# RPI_PICO_WH_PCB.net
KiCad netlist of a schematic drawn in EAGLE
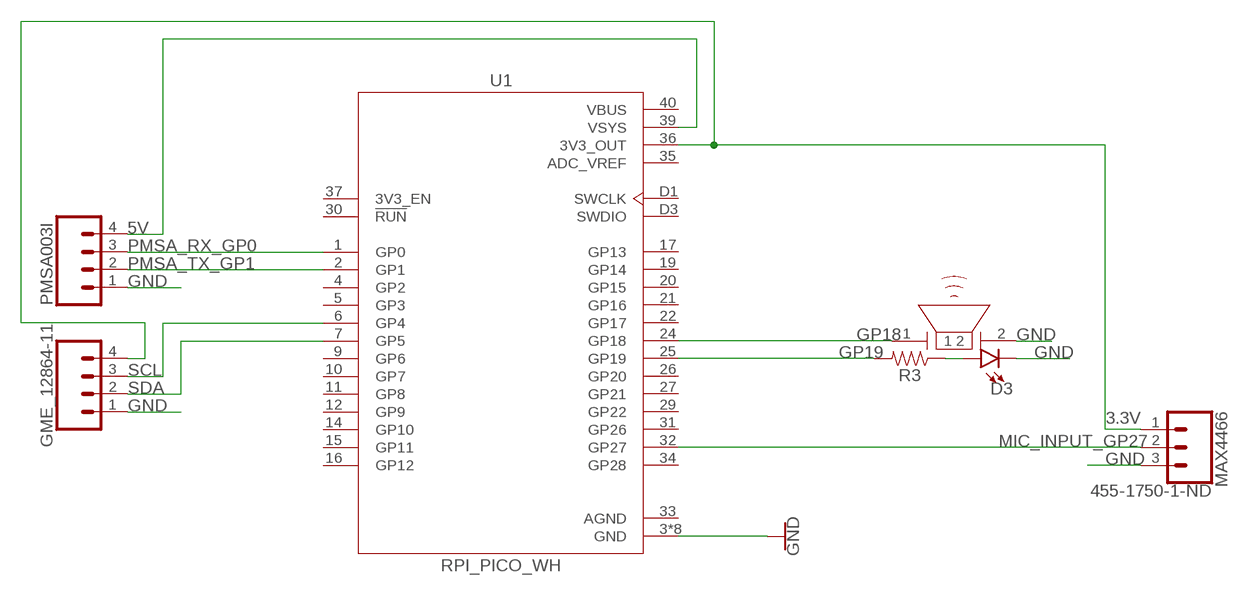
[diagram p0: schematic, sheet 1]

(export (version "E")
  (design (tool "Eeschema 10.0.6"))
  (components
    (comp (ref "D3")
      (value "LED5MM")
      (footprint "eagle-import:LED_5MM")
      (libsource (lib "eagle-import") (part "LED5MM"))
    )
    (comp (ref "GME_12864-11")
      (value "CONN_04PTH")
      (footprint "eagle-import:1X04")
      (libsource (lib "eagle-import") (part "CONN_04PTH"))
    )
    (comp (ref "LS1")
      (value "PIEZO")
      (footprint "eagle-import:PIEZO")
      (libsource (lib "eagle-import") (part "PIEZO"))
    )
    (comp (ref "MAX4466")
      (value "455-1750-1-ND")
      (footprint "eagle-import:1X03")
      (libsource (lib "eagle-import") (part "CONN_03"))
    )
    (comp (ref "PMSA003I")
      (value "CONN_04PTH")
      (footprint "eagle-import:1X04")
      (libsource (lib "eagle-import") (part "CONN_04PTH"))
    )
    (comp (ref "R3")
      (value "RESISTORAXIAL-0.3")
      (footprint "eagle-import:AXIAL-0.3")
      (libsource (lib "eagle-import") (part "RESISTORAXIAL-0.3"))
    )
    (comp (ref "U1")
      (value "RPI_PICO_WH")
      (footprint "eagle-import:PI_PICO_WH")
      (fields (field (name "MANUFACTURER") "Raspberry Pi") (field (name "MPN") "SC0919"))
      (libsource (lib "eagle-import") (part "RPI_PICO_WH"))
    )
  )
  (nets
    (net (code "1") (name "/3.3V") (class "Default")
      (node (ref "GME_12864-11") (pin "4") (pinfunction "4_4") (pintype "passive"))
      (node (ref "MAX4466") (pin "1") (pinfunction "1_1") (pintype "passive"))
      (node (ref "U1") (pin "36") (pinfunction "3V3_OUT_36") (pintype "power_in"))
    )
    (net (code "2") (name "/5V") (class "Default")
      (node (ref "PMSA003I") (pin "4") (pinfunction "4_4") (pintype "passive"))
      (node (ref "U1") (pin "39") (pinfunction "VSYS_39") (pintype "power_in"))
    )
    (net (code "3") (name "/ADC_VREF") (class "Default")
      (node (ref "U1") (pin "35") (pinfunction "ADC_VREF_35") (pintype "power_in"))
    )
    (net (code "4") (name "/AGND") (class "Default")
      (node (ref "U1") (pin "33") (pinfunction "AGND_33") (pintype "power_in"))
    )
    (net (code "5") (name "/GP18") (class "Default")
      (node (ref "LS1") (pin "1") (pinfunction "1_1") (pintype "passive"))
      (node (ref "U1") (pin "24") (pinfunction "GP18_24") (pintype "bidirectional"))
    )
    (net (code "6") (name "/GP19") (class "Default")
      (node (ref "R3") (pin "P$2") (pinfunction "2_P$2") (pintype "passive"))
      (node (ref "U1") (pin "25") (pinfunction "GP19_25") (pintype "bidirectional"))
    )
    (net (code "7") (name "/MIC_INPUT_GP27") (class "Default")
      (node (ref "MAX4466") (pin "2") (pinfunction "2_2") (pintype "passive"))
      (node (ref "U1") (pin "32") (pinfunction "GP27_32") (pintype "bidirectional"))
    )
    (net (code "8") (name "/PMSA_RX_GP0") (class "Default")
      (node (ref "PMSA003I") (pin "3") (pinfunction "3_3") (pintype "passive"))
      (node (ref "U1") (pin "1") (pinfunction "GP0_1") (pintype "bidirectional"))
    )
    (net (code "9") (name "/PMSA_TX_GP1") (class "Default")
      (node (ref "PMSA003I") (pin "2") (pinfunction "2_2") (pintype "passive"))
      (node (ref "U1") (pin "2") (pinfunction "GP1_2") (pintype "bidirectional"))
    )
    (net (code "10") (name "/SCL") (class "Default")
      (node (ref "GME_12864-11") (pin "3") (pinfunction "3_3") (pintype "passive"))
      (node (ref "U1") (pin "6") (pinfunction "GP4_6") (pintype "bidirectional"))
    )
    (net (code "11") (name "/SDA") (class "Default")
      (node (ref "GME_12864-11") (pin "2") (pinfunction "2_2") (pintype "passive"))
      (node (ref "U1") (pin "7") (pinfunction "GP5_7") (pintype "bidirectional"))
    )
    (net (code "12") (name "/VBUS") (class "Default")
      (node (ref "U1") (pin "40") (pinfunction "VBUS_40") (pintype "power_in"))
    )
    (net (code "13") (name "GND") (class "Default")
      (node (ref "D3") (pin "K") (pinfunction "C_K") (pintype "passive"))
      (node (ref "GME_12864-11") (pin "1") (pinfunction "1_1") (pintype "passive"))
      (node (ref "LS1") (pin "2") (pinfunction "2_2") (pintype "passive"))
      (node (ref "MAX4466") (pin "3") (pinfunction "3_3") (pintype "passive"))
      (node (ref "PMSA003I") (pin "1") (pinfunction "1_1") (pintype "passive"))
      (node (ref "U1") (pin "13") (pinfunction "GND_13") (pintype "power_in"))
      (node (ref "U1") (pin "18") (pinfunction "GND_18") (pintype "power_in"))
      (node (ref "U1") (pin "23") (pinfunction "GND_23") (pintype "power_in"))
      (node (ref "U1") (pin "28") (pinfunction "GND_28") (pintype "power_in"))
      (node (ref "U1") (pin "3") (pinfunction "GND_3") (pintype "power_in"))
      (node (ref "U1") (pin "38") (pinfunction "GND_38") (pintype "power_in"))
      (node (ref "U1") (pin "8") (pinfunction "GND_8") (pintype "power_in"))
      (node (ref "U1") (pin "D2") (pinfunction "GND_D2") (pintype "power_in"))
    )
    (net (code "14") (name "Net-(R3-1)") (class "Default")
      (node (ref "D3") (pin "A") (pinfunction "A_A") (pintype "passive"))
      (node (ref "R3") (pin "P$1") (pinfunction "1_P$1") (pintype "passive"))
    )
    (net (code "15") (name "unconnected-(U1-3V3_EN-Pad37)") (class "Default")
      (node (ref "U1") (pin "37") (pinfunction "3V3_EN_37") (pintype "input"))
    )
    (net (code "16") (name "unconnected-(U1-GP2-Pad4)") (class "Default")
      (node (ref "U1") (pin "4") (pinfunction "GP2_4") (pintype "bidirectional"))
    )
    (net (code "17") (name "unconnected-(U1-GP3-Pad5)") (class "Default")
      (node (ref "U1") (pin "5") (pinfunction "GP3_5") (pintype "bidirectional"))
    )
    (net (code "18") (name "unconnected-(U1-GP6-Pad9)") (class "Default")
      (node (ref "U1") (pin "9") (pinfunction "GP6_9") (pintype "bidirectional"))
    )
    (net (code "19") (name "unconnected-(U1-GP7-Pad10)") (class "Default")
      (node (ref "U1") (pin "10") (pinfunction "GP7_10") (pintype "bidirectional"))
    )
    (net (code "20") (name "unconnected-(U1-GP8-Pad11)") (class "Default")
      (node (ref "U1") (pin "11") (pinfunction "GP8_11") (pintype "bidirectional"))
    )
    (net (code "21") (name "unconnected-(U1-GP9-Pad12)") (class "Default")
      (node (ref "U1") (pin "12") (pinfunction "GP9_12") (pintype "bidirectional"))
    )
    (net (code "22") (name "unconnected-(U1-GP10-Pad14)") (class "Default")
      (node (ref "U1") (pin "14") (pinfunction "GP10_14") (pintype "bidirectional"))
    )
    (net (code "23") (name "unconnected-(U1-GP11-Pad15)") (class "Default")
      (node (ref "U1") (pin "15") (pinfunction "GP11_15") (pintype "bidirectional"))
    )
    (net (code "24") (name "unconnected-(U1-GP12-Pad16)") (class "Default")
      (node (ref "U1") (pin "16") (pinfunction "GP12_16") (pintype "bidirectional"))
    )
    (net (code "25") (name "unconnected-(U1-GP13-Pad17)") (class "Default")
      (node (ref "U1") (pin "17") (pinfunction "GP13_17") (pintype "bidirectional"))
    )
    (net (code "26") (name "unconnected-(U1-GP14-Pad19)") (class "Default")
      (node (ref "U1") (pin "19") (pinfunction "GP14_19") (pintype "bidirectional"))
    )
    (net (code "27") (name "unconnected-(U1-GP15-Pad20)") (class "Default")
      (node (ref "U1") (pin "20") (pinfunction "GP15_20") (pintype "bidirectional"))
    )
    (net (code "28") (name "unconnected-(U1-GP16-Pad21)") (class "Default")
      (node (ref "U1") (pin "21") (pinfunction "GP16_21") (pintype "bidirectional"))
    )
    (net (code "29") (name "unconnected-(U1-GP17-Pad22)") (class "Default")
      (node (ref "U1") (pin "22") (pinfunction "GP17_22") (pintype "bidirectional"))
    )
    (net (code "30") (name "unconnected-(U1-GP20-Pad26)") (class "Default")
      (node (ref "U1") (pin "26") (pinfunction "GP20_26") (pintype "bidirectional"))
    )
    (net (code "31") (name "unconnected-(U1-GP21-Pad27)") (class "Default")
      (node (ref "U1") (pin "27") (pinfunction "GP21_27") (pintype "bidirectional"))
    )
    (net (code "32") (name "unconnected-(U1-GP22-Pad29)") (class "Default")
      (node (ref "U1") (pin "29") (pinfunction "GP22_29") (pintype "bidirectional"))
    )
    (net (code "33") (name "unconnected-(U1-GP26-Pad31)") (class "Default")
      (node (ref "U1") (pin "31") (pinfunction "GP26_31") (pintype "bidirectional"))
    )
    (net (code "34") (name "unconnected-(U1-GP28-Pad34)") (class "Default")
      (node (ref "U1") (pin "34") (pinfunction "GP28_34") (pintype "bidirectional"))
    )
    (net (code "35") (name "unconnected-(U1-SWCLK-PadD1)") (class "Default")
      (node (ref "U1") (pin "D1") (pinfunction "SWCLK_D1") (pintype "input"))
    )
    (net (code "36") (name "unconnected-(U1-SWDIO-PadD3)") (class "Default")
      (node (ref "U1") (pin "D3") (pinfunction "SWDIO_D3") (pintype "bidirectional"))
    )
    (net (code "37") (name "unconnected-(U1-~{RUN}-Pad30)") (class "Default")
      (node (ref "U1") (pin "30") (pinfunction "~{RUN}_30") (pintype "input"))
    )
  )
)
